# octanis_eps_v03.net
KiCad netlist of a schematic drawn in EAGLE
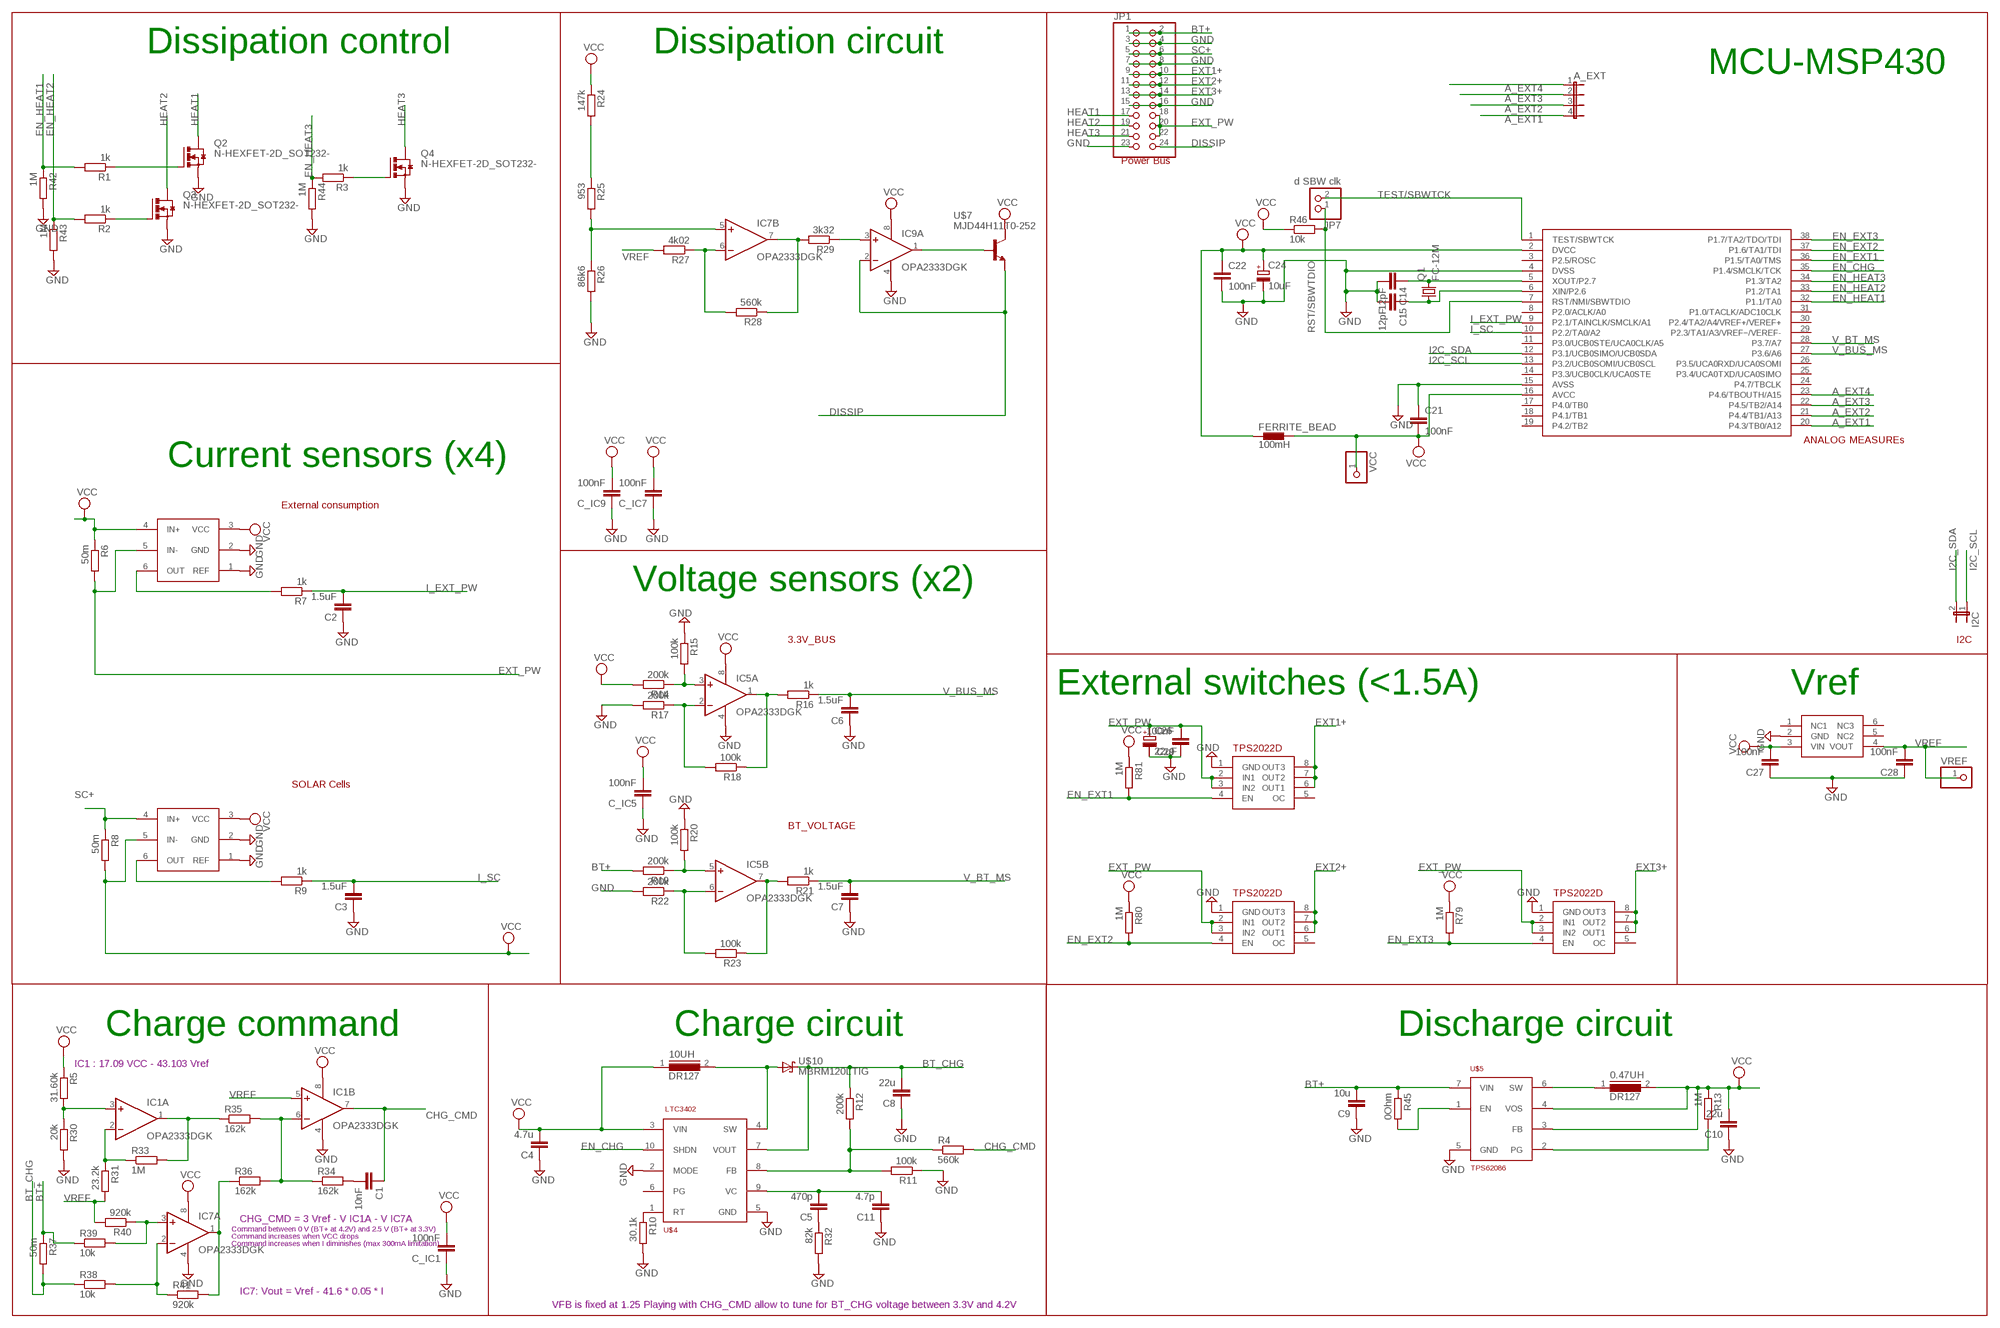
[diagram p0: schematic, sheet 1]

(export (version "E")
  (design (tool "Eeschema 10.0.6"))
  (components
    (comp (ref "0.47UH")
      (value "DR127")
      (footprint "eagle-import:DR127")
      (libsource (lib "eagle-import") (part "DR127"))
    )
    (comp (ref "10UH")
      (value "DR127")
      (footprint "eagle-import:DR127")
      (libsource (lib "eagle-import") (part "DR127"))
    )
    (comp (ref "A_EXT")
      (value "JP4E")
      (footprint "eagle-import:JP4")
      (libsource (lib "eagle-import") (part "JP4E"))
    )
    (comp (ref "C1")
      (value "10nF")
      (footprint "eagle-import:C0603")
      (libsource (lib "eagle-import") (part "C-EUC0603"))
    )
    (comp (ref "C2")
      (value "1.5uF")
      (footprint "eagle-import:C0603")
      (libsource (lib "eagle-import") (part "C-EUC0603"))
    )
    (comp (ref "C3")
      (value "1.5uF")
      (footprint "eagle-import:C0603")
      (libsource (lib "eagle-import") (part "C-EUC0603"))
    )
    (comp (ref "C4")
      (value "4.7u")
      (footprint "eagle-import:C1206")
      (libsource (lib "eagle-import") (part "C-EUC1206"))
    )
    (comp (ref "C5")
      (value "470p")
      (footprint "eagle-import:C0603")
      (libsource (lib "eagle-import") (part "C-EUC0603"))
    )
    (comp (ref "C6")
      (value "1.5uF")
      (footprint "eagle-import:C0603")
      (libsource (lib "eagle-import") (part "C-EUC0603"))
    )
    (comp (ref "C7")
      (value "1.5uF")
      (footprint "eagle-import:C0603")
      (libsource (lib "eagle-import") (part "C-EUC0603"))
    )
    (comp (ref "C8")
      (value "22u")
      (footprint "eagle-import:C0603")
      (libsource (lib "eagle-import") (part "C-EUC0603"))
    )
    (comp (ref "C9")
      (value "10u")
      (footprint "eagle-import:C1206")
      (libsource (lib "eagle-import") (part "C-EUC1206"))
    )
    (comp (ref "C10")
      (value "22u")
      (footprint "eagle-import:C1206")
      (libsource (lib "eagle-import") (part "C-EUC1206"))
    )
    (comp (ref "C11")
      (value "4.7p")
      (footprint "eagle-import:C0603")
      (libsource (lib "eagle-import") (part "C-EUC0603"))
    )
    (comp (ref "C14")
      (value "12pF")
      (footprint "eagle-import:C0603")
      (libsource (lib "eagle-import") (part "C-EUC0603"))
    )
    (comp (ref "C15")
      (value "12pF")
      (footprint "eagle-import:C0603")
      (libsource (lib "eagle-import") (part "C-EUC0603"))
    )
    (comp (ref "C21")
      (value "100nF")
      (footprint "eagle-import:C0603")
      (libsource (lib "eagle-import") (part "C-EUC0603"))
    )
    (comp (ref "C22")
      (value "100nF")
      (footprint "eagle-import:C0603")
      (libsource (lib "eagle-import") (part "C-EUC0603"))
    )
    (comp (ref "C24")
      (value "10uF")
      (footprint "eagle-import:A_3216-18R")
      (libsource (lib "eagle-import") (part "CPOL-EUA/3216-18R"))
    )
    (comp (ref "C26")
      (value "22uF")
      (footprint "eagle-import:A_3216-18R")
      (libsource (lib "eagle-import") (part "CPOL-EUA/3216-18R"))
    )
    (comp (ref "C27")
      (value "100nF")
      (footprint "eagle-import:C0603")
      (libsource (lib "eagle-import") (part "C-EUC0603"))
    )
    (comp (ref "C28")
      (value "100nF")
      (footprint "eagle-import:C0603")
      (libsource (lib "eagle-import") (part "C-EUC0603"))
    )
    (comp (ref "C29")
      (value "100nF")
      (footprint "eagle-import:C0603")
      (libsource (lib "eagle-import") (part "C-EUC0603"))
    )
    (comp (ref "C_IC1")
      (value "100nF")
      (footprint "eagle-import:C0603")
      (libsource (lib "eagle-import") (part "C-EUC0603"))
    )
    (comp (ref "C_IC5")
      (value "100nF")
      (footprint "eagle-import:C0603")
      (libsource (lib "eagle-import") (part "C-EUC0603"))
    )
    (comp (ref "C_IC7")
      (value "100nF")
      (footprint "eagle-import:C0603")
      (libsource (lib "eagle-import") (part "C-EUC0603"))
    )
    (comp (ref "C_IC9")
      (value "100nF")
      (footprint "eagle-import:C0603")
      (libsource (lib "eagle-import") (part "C-EUC0603"))
    )
    (comp (ref "FERRITE_BEAD")
      (value "100mH")
      (footprint "eagle-import:0402")
      (libsource (lib "eagle-import") (part "BLM15HD601SN1"))
    )
    (comp (ref "I2C")
      (value "JP1E")
      (footprint "eagle-import:JP1")
      (libsource (lib "eagle-import") (part "JP1E"))
    )
    (comp (ref "IC1")
      (value "OPA2333DGK")
      (footprint "eagle-import:MSOP08")
      (libsource (lib "eagle-import") (part "OPA2333DGK"))
    )
    (comp (ref "IC5")
      (value "OPA2333DGK")
      (footprint "eagle-import:MSOP08")
      (libsource (lib "eagle-import") (part "OPA2333DGK"))
    )
    (comp (ref "IC7")
      (value "OPA2333DGK")
      (footprint "eagle-import:MSOP08")
      (libsource (lib "eagle-import") (part "OPA2333DGK"))
    )
    (comp (ref "IC9")
      (value "OPA2333DGK")
      (footprint "eagle-import:MSOP08")
      (libsource (lib "eagle-import") (part "OPA2333DGK"))
    )
    (comp (ref "JP1")
      (value "PINHD-2X12")
      (footprint "eagle-import:2X12")
      (libsource (lib "eagle-import") (part "PINHD-2X12"))
    )
    (comp (ref "JP7")
      (value "d SBW clk")
      (footprint "eagle-import:1X02")
      (libsource (lib "eagle-import") (part "PINHD-1X2"))
    )
    (comp (ref "Q1")
      (value "FC-12M")
      (footprint "eagle-import:FC-12M")
      (libsource (lib "eagle-import") (part "FC-12M"))
    )
    (comp (ref "Q2")
      (value "N-HEXFET-2D_SOT232-")
      (footprint "eagle-import:SOT223")
      (libsource (lib "eagle-import") (part "N-HEXFET-2D_?-SOT232"))
    )
    (comp (ref "Q3")
      (value "N-HEXFET-2D_SOT232-")
      (footprint "eagle-import:SOT223")
      (libsource (lib "eagle-import") (part "N-HEXFET-2D_?-SOT232"))
    )
    (comp (ref "Q4")
      (value "N-HEXFET-2D_SOT232-")
      (footprint "eagle-import:SOT223")
      (libsource (lib "eagle-import") (part "N-HEXFET-2D_?-SOT232"))
    )
    (comp (ref "R1")
      (value "1k")
      (footprint "eagle-import:R0603")
      (libsource (lib "eagle-import") (part "R-EU_R0603"))
    )
    (comp (ref "R2")
      (value "1k")
      (footprint "eagle-import:R0603")
      (libsource (lib "eagle-import") (part "R-EU_R0603"))
    )
    (comp (ref "R3")
      (value "1k")
      (footprint "eagle-import:R0603")
      (libsource (lib "eagle-import") (part "R-EU_R0603"))
    )
    (comp (ref "R4")
      (value "560k")
      (footprint "eagle-import:R0603")
      (libsource (lib "eagle-import") (part "R-EU_R0603"))
    )
    (comp (ref "R5")
      (value "31.60k")
      (footprint "eagle-import:R0603")
      (libsource (lib "eagle-import") (part "R-EU_R0603"))
    )
    (comp (ref "R6")
      (value "50m")
      (footprint "eagle-import:R1206")
      (libsource (lib "eagle-import") (part "R-EU_R1206"))
    )
    (comp (ref "R7")
      (value "1k")
      (footprint "eagle-import:R0603")
      (libsource (lib "eagle-import") (part "R-EU_R0603"))
    )
    (comp (ref "R8")
      (value "50m")
      (footprint "eagle-import:R1206")
      (libsource (lib "eagle-import") (part "R-EU_R1206"))
    )
    (comp (ref "R9")
      (value "1k")
      (footprint "eagle-import:R0603")
      (libsource (lib "eagle-import") (part "R-EU_R0603"))
    )
    (comp (ref "R10")
      (value "30.1k")
      (footprint "eagle-import:R0603")
      (libsource (lib "eagle-import") (part "R-EU_R0603"))
    )
    (comp (ref "R11")
      (value "100k")
      (footprint "eagle-import:R0603")
      (libsource (lib "eagle-import") (part "R-EU_R0603"))
    )
    (comp (ref "R12")
      (value "200k")
      (footprint "eagle-import:R0603")
      (libsource (lib "eagle-import") (part "R-EU_R0603"))
    )
    (comp (ref "R13")
      (value "1M")
      (footprint "eagle-import:R0603")
      (libsource (lib "eagle-import") (part "R-EU_R0603"))
    )
    (comp (ref "R14")
      (value "200k")
      (footprint "eagle-import:R0603")
      (libsource (lib "eagle-import") (part "R-EU_R0603"))
    )
    (comp (ref "R15")
      (value "100k")
      (footprint "eagle-import:R0603")
      (libsource (lib "eagle-import") (part "R-EU_R0603"))
    )
    (comp (ref "R16")
      (value "1k")
      (footprint "eagle-import:R0603")
      (libsource (lib "eagle-import") (part "R-EU_R0603"))
    )
    (comp (ref "R17")
      (value "200k")
      (footprint "eagle-import:R0603")
      (libsource (lib "eagle-import") (part "R-EU_R0603"))
    )
    (comp (ref "R18")
      (value "100k")
      (footprint "eagle-import:R0603")
      (libsource (lib "eagle-import") (part "R-EU_R0603"))
    )
    (comp (ref "R19")
      (value "200k")
      (footprint "eagle-import:R0603")
      (libsource (lib "eagle-import") (part "R-EU_R0603"))
    )
    (comp (ref "R20")
      (value "100k")
      (footprint "eagle-import:R0603")
      (libsource (lib "eagle-import") (part "R-EU_R0603"))
    )
    (comp (ref "R21")
      (value "1k")
      (footprint "eagle-import:R0603")
      (libsource (lib "eagle-import") (part "R-EU_R0603"))
    )
    (comp (ref "R22")
      (value "200k")
      (footprint "eagle-import:R0603")
      (libsource (lib "eagle-import") (part "R-EU_R0603"))
    )
    (comp (ref "R23")
      (value "100k")
      (footprint "eagle-import:R0603")
      (libsource (lib "eagle-import") (part "R-EU_R0603"))
    )
    (comp (ref "R24")
      (value "147k")
      (footprint "eagle-import:R0603")
      (libsource (lib "eagle-import") (part "R-EU_R0603"))
    )
    (comp (ref "R25")
      (value "953")
      (footprint "eagle-import:R0603")
      (libsource (lib "eagle-import") (part "R-EU_R0603"))
    )
    (comp (ref "R26")
      (value "86k6")
      (footprint "eagle-import:R0603")
      (libsource (lib "eagle-import") (part "R-EU_R0603"))
    )
    (comp (ref "R27")
      (value "4k02")
      (footprint "eagle-import:R0603")
      (libsource (lib "eagle-import") (part "R-EU_R0603"))
    )
    (comp (ref "R28")
      (value "560k")
      (footprint "eagle-import:R0603")
      (libsource (lib "eagle-import") (part "R-EU_R0603"))
    )
    (comp (ref "R29")
      (value "3k32")
      (footprint "eagle-import:R0603")
      (libsource (lib "eagle-import") (part "R-EU_R0603"))
    )
    (comp (ref "R30")
      (value "20k")
      (footprint "eagle-import:R0603")
      (libsource (lib "eagle-import") (part "R-EU_R0603"))
    )
    (comp (ref "R31")
      (value "23.2k")
      (footprint "eagle-import:R0603")
      (libsource (lib "eagle-import") (part "R-EU_R0603"))
    )
    (comp (ref "R32")
      (value "82k")
      (footprint "eagle-import:R0603")
      (libsource (lib "eagle-import") (part "R-EU_R0603"))
    )
    (comp (ref "R33")
      (value "1M")
      (footprint "eagle-import:R0603")
      (libsource (lib "eagle-import") (part "R-EU_R0603"))
    )
    (comp (ref "R34")
      (value "162k")
      (footprint "eagle-import:R0603")
      (libsource (lib "eagle-import") (part "R-EU_R0603"))
    )
    (comp (ref "R35")
      (value "162k")
      (footprint "eagle-import:R0603")
      (libsource (lib "eagle-import") (part "R-EU_R0603"))
    )
    (comp (ref "R36")
      (value "162k")
      (footprint "eagle-import:R0603")
      (libsource (lib "eagle-import") (part "R-EU_R0603"))
    )
    (comp (ref "R37")
      (value "50m")
      (footprint "eagle-import:R1206")
      (libsource (lib "eagle-import") (part "R-EU_R1206"))
    )
    (comp (ref "R38")
      (value "10k")
      (footprint "eagle-import:R0603")
      (libsource (lib "eagle-import") (part "R-EU_R0603"))
    )
    (comp (ref "R39")
      (value "10k")
      (footprint "eagle-import:R0603")
      (libsource (lib "eagle-import") (part "R-EU_R0603"))
    )
    (comp (ref "R40")
      (value "920k")
      (footprint "eagle-import:R0603")
      (libsource (lib "eagle-import") (part "R-EU_R0603"))
    )
    (comp (ref "R41")
      (value "920k")
      (footprint "eagle-import:R0603")
      (libsource (lib "eagle-import") (part "R-EU_R0603"))
    )
    (comp (ref "R42")
      (value "1M")
      (footprint "eagle-import:R0603")
      (libsource (lib "eagle-import") (part "R-EU_R0603"))
    )
    (comp (ref "R43")
      (value "1M")
      (footprint "eagle-import:R0603")
      (libsource (lib "eagle-import") (part "R-EU_R0603"))
    )
    (comp (ref "R44")
      (value "1M")
      (footprint "eagle-import:R0603")
      (libsource (lib "eagle-import") (part "R-EU_R0603"))
    )
    (comp (ref "R45")
      (value "0Ohm")
      (footprint "eagle-import:R0603")
      (libsource (lib "eagle-import") (part "R-EU_R0603"))
    )
    (comp (ref "R46")
      (value "10k")
      (footprint "eagle-import:R0603")
      (libsource (lib "eagle-import") (part "R-EU_R0603"))
    )
    (comp (ref "R79")
      (value "1M")
      (footprint "eagle-import:R0603")
      (libsource (lib "eagle-import") (part "R-EU_R0603"))
    )
    (comp (ref "R80")
      (value "1M")
      (footprint "eagle-import:R0603")
      (libsource (lib "eagle-import") (part "R-EU_R0603"))
    )
    (comp (ref "R81")
      (value "1M")
      (footprint "eagle-import:R0603")
      (libsource (lib "eagle-import") (part "R-EU_R0603"))
    )
    (comp (ref "U$2")
      (value "INA213")
      (footprint "eagle-import:SC70-6")
      (libsource (lib "eagle-import") (part "INA213"))
    )
    (comp (ref "U$3")
      (value "INA213")
      (footprint "eagle-import:SC70-6")
      (libsource (lib "eagle-import") (part "INA213"))
    )
    (comp (ref "U$4")
      (value "LTC3402")
      (footprint "eagle-import:MSOP10")
      (libsource (lib "eagle-import") (part "LTC3402"))
    )
    (comp (ref "U$5")
      (value "TPS62086")
      (footprint "eagle-import:QFN-7")
      (libsource (lib "eagle-import") (part "TPS62086"))
    )
    (comp (ref "U$6")
      (value "MSP430G2544")
      (footprint "eagle-import:TSSOP38_MSPGXX44_SERIES")
      (libsource (lib "eagle-import") (part "MSP430G2544"))
    )
    (comp (ref "U$7")
      (value "MJD44H11T0-252")
      (footprint "eagle-import:TO252")
      (libsource (lib "eagle-import") (part "MJD44H11T0-252"))
    )
    (comp (ref "U$10")
      (value "MBRM120LTIG")
      (footprint "eagle-import:DO216AA")
      (libsource (lib "eagle-import") (part "MBRM120LTIG"))
    )
    (comp (ref "U$16")
      (value "TPS2022D")
      (footprint "eagle-import:SO8")
      (libsource (lib "eagle-import") (part "TPS2022D"))
    )
    (comp (ref "U$17")
      (value "TPS2022D")
      (footprint "eagle-import:SO8")
      (libsource (lib "eagle-import") (part "TPS2022D"))
    )
    (comp (ref "U$18")
      (value "TPS2022D")
      (footprint "eagle-import:SO8")
      (libsource (lib "eagle-import") (part "TPS2022D"))
    )
    (comp (ref "U$19")
      (value "ADR127B")
      (footprint "eagle-import:TSOT23-6")
      (libsource (lib "eagle-import") (part "ADR127B"))
    )
    (comp (ref "VCC")
      (value "PINHD-1X1")
      (footprint "eagle-import:1X01")
      (libsource (lib "eagle-import") (part "PINHD-1X1"))
    )
    (comp (ref "VREF")
      (value "PINHD-1X1")
      (footprint "eagle-import:1X01")
      (libsource (lib "eagle-import") (part "PINHD-1X1"))
    )
  )
  (nets
    (net (code "1") (name "/A_EXT1") (class "Default")
      (node (ref "A_EXT") (pin "4") (pinfunction "4_4") (pintype "passive"))
      (node (ref "U$6") (pin "20") (pinfunction "P4.3/TB0/A12_20") (pintype "bidirectional"))
    )
    (net (code "2") (name "/A_EXT2") (class "Default")
      (node (ref "A_EXT") (pin "3") (pinfunction "3_3") (pintype "passive"))
      (node (ref "U$6") (pin "21") (pinfunction "P4.4/TB1/A13_21") (pintype "bidirectional"))
    )
    (net (code "3") (name "/A_EXT3") (class "Default")
      (node (ref "A_EXT") (pin "2") (pinfunction "2_2") (pintype "passive"))
      (node (ref "U$6") (pin "22") (pinfunction "P4.5/TB2/A14_22") (pintype "bidirectional"))
    )
    (net (code "4") (name "/A_EXT4") (class "Default")
      (node (ref "A_EXT") (pin "1") (pinfunction "1_1") (pintype "passive"))
      (node (ref "U$6") (pin "23") (pinfunction "P4.6/TBOUTH/A15_23") (pintype "bidirectional"))
    )
    (net (code "5") (name "/BT+") (class "Default")
      (node (ref "C9") (pin "2") (pinfunction "2_2") (pintype "passive"))
      (node (ref "JP1") (pin "1") (pinfunction "1_1") (pintype "passive"))
      (node (ref "JP1") (pin "2") (pinfunction "2_2") (pintype "passive"))
      (node (ref "R19") (pin "2") (pinfunction "2_2") (pintype "passive"))
      (node (ref "R37") (pin "1") (pinfunction "1_1") (pintype "passive"))
      (node (ref "R39") (pin "1") (pinfunction "1_1") (pintype "passive"))
      (node (ref "R45") (pin "1") (pinfunction "1_1") (pintype "passive"))
      (node (ref "U$5") (pin "7") (pinfunction "VIN_7") (pintype "bidirectional"))
    )
    (net (code "6") (name "/BT_CHG") (class "Default")
      (node (ref "C8") (pin "2") (pinfunction "2_2") (pintype "passive"))
      (node (ref "R12") (pin "1") (pinfunction "1_1") (pintype "passive"))
      (node (ref "R37") (pin "2") (pinfunction "2_2") (pintype "passive"))
      (node (ref "R38") (pin "1") (pinfunction "1_1") (pintype "passive"))
      (node (ref "U$10") (pin "C") (pinfunction "K_C") (pintype "passive"))
      (node (ref "U$4") (pin "7") (pinfunction "VOUT_7") (pintype "bidirectional"))
    )
    (net (code "7") (name "/CHG_CMD") (class "Default")
      (node (ref "C1") (pin "1") (pinfunction "1_1") (pintype "passive"))
      (node (ref "IC1") (pin "7") (pinfunction "OUT_7") (pintype "output"))
      (node (ref "R4") (pin "2") (pinfunction "2_2") (pintype "passive"))
    )
    (net (code "8") (name "/DISSIP") (class "Default")
      (node (ref "IC9") (pin "2") (pinfunction "-IN_2") (pintype "input"))
      (node (ref "JP1") (pin "24") (pinfunction "24_24") (pintype "passive"))
      (node (ref "U$7") (pin "3") (pinfunction "E_3") (pintype "passive"))
    )
    (net (code "9") (name "/EN_CHG") (class "Default")
      (node (ref "U$4") (pin "10") (pinfunction "SHDN_10") (pintype "bidirectional"))
      (node (ref "U$6") (pin "35") (pinfunction "P1.4/SMCLK/TCK_35") (pintype "bidirectional"))
    )
    (net (code "10") (name "/EN_EXT1") (class "Default")
      (node (ref "R81") (pin "2") (pinfunction "2_2") (pintype "passive"))
      (node (ref "U$16") (pin "4") (pinfunction "EN_4") (pintype "bidirectional"))
      (node (ref "U$6") (pin "36") (pinfunction "P1.5/TA0/TMS_36") (pintype "bidirectional"))
    )
    (net (code "11") (name "/EN_EXT2") (class "Default")
      (node (ref "R80") (pin "2") (pinfunction "2_2") (pintype "passive"))
      (node (ref "U$17") (pin "4") (pinfunction "EN_4") (pintype "bidirectional"))
      (node (ref "U$6") (pin "37") (pinfunction "P1.6/TA1/TDI_37") (pintype "bidirectional"))
    )
    (net (code "12") (name "/EN_EXT3") (class "Default")
      (node (ref "R79") (pin "2") (pinfunction "2_2") (pintype "passive"))
      (node (ref "U$18") (pin "4") (pinfunction "EN_4") (pintype "bidirectional"))
      (node (ref "U$6") (pin "38") (pinfunction "P1.7/TA2/TDO/TDI_38") (pintype "bidirectional"))
    )
    (net (code "13") (name "/EN_HEAT1") (class "Default")
      (node (ref "R1") (pin "2") (pinfunction "2_2") (pintype "passive"))
      (node (ref "R42") (pin "1") (pinfunction "1_1") (pintype "passive"))
      (node (ref "U$6") (pin "32") (pinfunction "P1.1/TA0_32") (pintype "bidirectional"))
    )
    (net (code "14") (name "/EN_HEAT2") (class "Default")
      (node (ref "R2") (pin "2") (pinfunction "2_2") (pintype "passive"))
      (node (ref "R43") (pin "1") (pinfunction "1_1") (pintype "passive"))
      (node (ref "U$6") (pin "33") (pinfunction "P1.2/TA1_33") (pintype "bidirectional"))
    )
    (net (code "15") (name "/EN_HEAT3") (class "Default")
      (node (ref "R3") (pin "2") (pinfunction "2_2") (pintype "passive"))
      (node (ref "R44") (pin "1") (pinfunction "1_1") (pintype "passive"))
      (node (ref "U$6") (pin "34") (pinfunction "P1.3/TA2_34") (pintype "bidirectional"))
    )
    (net (code "16") (name "/EXT1+") (class "Default")
      (node (ref "JP1") (pin "10") (pinfunction "10_10") (pintype "passive"))
      (node (ref "JP1") (pin "9") (pinfunction "9_9") (pintype "passive"))
      (node (ref "U$16") (pin "6") (pinfunction "OUT1_6") (pintype "bidirectional"))
      (node (ref "U$16") (pin "7") (pinfunction "OUT2_7") (pintype "bidirectional"))
      (node (ref "U$16") (pin "8") (pinfunction "OUT3_8") (pintype "bidirectional"))
    )
    (net (code "17") (name "/EXT2+") (class "Default")
      (node (ref "JP1") (pin "11") (pinfunction "11_11") (pintype "passive"))
      (node (ref "JP1") (pin "12") (pinfunction "12_12") (pintype "passive"))
      (node (ref "U$17") (pin "6") (pinfunction "OUT1_6") (pintype "bidirectional"))
      (node (ref "U$17") (pin "7") (pinfunction "OUT2_7") (pintype "bidirectional"))
      (node (ref "U$17") (pin "8") (pinfunction "OUT3_8") (pintype "bidirectional"))
    )
    (net (code "18") (name "/EXT3+") (class "Default")
      (node (ref "JP1") (pin "13") (pinfunction "13_13") (pintype "passive"))
      (node (ref "JP1") (pin "14") (pinfunction "14_14") (pintype "passive"))
      (node (ref "U$18") (pin "6") (pinfunction "OUT1_6") (pintype "bidirectional"))
      (node (ref "U$18") (pin "7") (pinfunction "OUT2_7") (pintype "bidirectional"))
      (node (ref "U$18") (pin "8") (pinfunction "OUT3_8") (pintype "bidirectional"))
    )
    (net (code "19") (name "/EXT_PW") (class "Default")
      (node (ref "C26") (pin "+") (pinfunction "+_+") (pintype "passive"))
      (node (ref "C29") (pin "2") (pinfunction "2_2") (pintype "passive"))
      (node (ref "JP1") (pin "18") (pinfunction "18_18") (pintype "passive"))
      (node (ref "JP1") (pin "20") (pinfunction "20_20") (pintype "passive"))
      (node (ref "JP1") (pin "22") (pinfunction "22_22") (pintype "passive"))
      (node (ref "R6") (pin "2") (pinfunction "2_2") (pintype "passive"))
      (node (ref "U$16") (pin "2") (pinfunction "IN1_2") (pintype "bidirectional"))
      (node (ref "U$16") (pin "3") (pinfunction "IN2_3") (pintype "bidirectional"))
      (node (ref "U$17") (pin "2") (pinfunction "IN1_2") (pintype "bidirectional"))
      (node (ref "U$17") (pin "3") (pinfunction "IN2_3") (pintype "bidirectional"))
      (node (ref "U$18") (pin "2") (pinfunction "IN1_2") (pintype "bidirectional"))
      (node (ref "U$18") (pin "3") (pinfunction "IN2_3") (pintype "bidirectional"))
      (node (ref "U$2") (pin "5") (pinfunction "IN-_5") (pintype "bidirectional"))
    )
    (net (code "20") (name "/HEAT1") (class "Default")
      (node (ref "JP1") (pin "17") (pinfunction "17_17") (pintype "passive"))
      (node (ref "Q2") (pin "2") (pinfunction "D_2") (pintype "passive"))
      (node (ref "Q2") (pin "4") (pinfunction "D_4") (pintype "passive"))
    )
    (net (code "21") (name "/HEAT2") (class "Default")
      (node (ref "JP1") (pin "19") (pinfunction "19_19") (pintype "passive"))
      (node (ref "Q3") (pin "2") (pinfunction "D_2") (pintype "passive"))
      (node (ref "Q3") (pin "4") (pinfunction "D_4") (pintype "passive"))
    )
    (net (code "22") (name "/HEAT3") (class "Default")
      (node (ref "JP1") (pin "21") (pinfunction "21_21") (pintype "passive"))
      (node (ref "Q4") (pin "2") (pinfunction "D_2") (pintype "passive"))
      (node (ref "Q4") (pin "4") (pinfunction "D_4") (pintype "passive"))
    )
    (net (code "23") (name "/I2C_SCL") (class "Default")
      (node (ref "I2C") (pin "1") (pinfunction "1_1") (pintype "passive"))
      (node (ref "U$6") (pin "13") (pinfunction "P3.2/UCB0SOMI/UCB0SCL_13") (pintype "bidirectional"))
    )
    (net (code "24") (name "/I2C_SDA") (class "Default")
      (node (ref "I2C") (pin "2") (pinfunction "2_2") (pintype "passive"))
      (node (ref "U$6") (pin "12") (pinfunction "P3.1/UCB0SIMO/UCB0SDA_12") (pintype "bidirectional"))
    )
    (net (code "25") (name "/I_EXT_PW") (class "Default")
      (node (ref "C2") (pin "2") (pinfunction "2_2") (pintype "passive"))
      (node (ref "R7") (pin "1") (pinfunction "1_1") (pintype "passive"))
      (node (ref "U$6") (pin "9") (pinfunction "P2.1/TAINCLK/SMCLK/A1_9") (pintype "bidirectional"))
    )
    (net (code "26") (name "/I_SC") (class "Default")
      (node (ref "C3") (pin "2") (pinfunction "2_2") (pintype "passive"))
      (node (ref "R9") (pin "1") (pinfunction "1_1") (pintype "passive"))
      (node (ref "U$6") (pin "10") (pinfunction "P2.2/TA0/A2_10") (pintype "bidirectional"))
    )
    (net (code "27") (name "/RST{slash}SBWTDIO") (class "Default")
      (node (ref "JP7") (pin "1") (pinfunction "1_1") (pintype "passive"))
      (node (ref "R46") (pin "2") (pinfunction "2_2") (pintype "passive"))
      (node (ref "U$6") (pin "7") (pinfunction "RST/NMI/SBWTDIO_7") (pintype "bidirectional"))
    )
    (net (code "28") (name "/SC+") (class "Default")
      (node (ref "JP1") (pin "5") (pinfunction "5_5") (pintype "passive"))
      (node (ref "JP1") (pin "6") (pinfunction "6_6") (pintype "passive"))
      (node (ref "R8") (pin "1") (pinfunction "1_1") (pintype "passive"))
      (node (ref "U$3") (pin "4") (pinfunction "IN+_4") (pintype "bidirectional"))
    )
    (net (code "29") (name "/TEST{slash}SBWTCK") (class "Default")
      (node (ref "JP7") (pin "2") (pinfunction "2_2") (pintype "passive"))
      (node (ref "U$6") (pin "1") (pinfunction "TEST/SBWTCK_1") (pintype "bidirectional"))
    )
    (net (code "30") (name "/VREF") (class "Default")
      (node (ref "C28") (pin "2") (pinfunction "2_2") (pintype "passive"))
      (node (ref "IC1") (pin "5") (pinfunction "+IN_5") (pintype "input"))
      (node (ref "R27") (pin "2") (pinfunction "2_2") (pintype "passive"))
      (node (ref "R31") (pin "2") (pinfunction "2_2") (pintype "passive"))
      (node (ref "R40") (pin "2") (pinfunction "2_2") (pintype "passive"))
      (node (ref "U$19") (pin "4") (pinfunction "VOUT_4") (pintype "bidirectional"))
      (node (ref "VREF") (pin "1") (pinfunction "1_1") (pintype "passive"))
    )
    (net (code "31") (name "/V_BT_MS") (class "Default")
      (node (ref "C7") (pin "2") (pinfunction "2_2") (pintype "passive"))
      (node (ref "R21") (pin "1") (pinfunction "1_1") (pintype "passive"))
      (node (ref "U$6") (pin "28") (pinfunction "P3.7/A7_28") (pintype "bidirectional"))
    )
    (net (code "32") (name "/V_BUS_MS") (class "Default")
      (node (ref "C6") (pin "2") (pinfunction "2_2") (pintype "passive"))
      (node (ref "R16") (pin "1") (pinfunction "1_1") (pintype "passive"))
      (node (ref "U$6") (pin "27") (pinfunction "P3.6/A6_27") (pintype "bidirectional"))
    )
    (net (code "33") (name "GND") (class "Default")
      (node (ref "C10") (pin "1") (pinfunction "1_1") (pintype "passive"))
      (node (ref "C11") (pin "1") (pinfunction "1_1") (pintype "passive"))
      (node (ref "C14") (pin "2") (pinfunction "2_2") (pintype "passive"))
      (node (ref "C15") (pin "2") (pinfunction "2_2") (pintype "passive"))
      (node (ref "C2") (pin "1") (pinfunction "1_1") (pintype "passive"))
      (node (ref "C21") (pin "1") (pinfunction "1_1") (pintype "passive"))
      (node (ref "C22") (pin "2") (pinfunction "2_2") (pintype "passive"))
      (node (ref "C24") (pin "-") (pinfunction "-_-") (pintype "passive"))
      (node (ref "C26") (pin "-") (pinfunction "-_-") (pintype "passive"))
      (node (ref "C27") (pin "1") (pinfunction "1_1") (pintype "passive"))
      (node (ref "C28") (pin "1") (pinfunction "1_1") (pintype "passive"))
      (node (ref "C29") (pin "1") (pinfunction "1_1") (pintype "passive"))
      (node (ref "C3") (pin "1") (pinfunction "1_1") (pintype "passive"))
      (node (ref "C4") (pin "1") (pinfunction "1_1") (pintype "passive"))
      (node (ref "C6") (pin "1") (pinfunction "1_1") (pintype "passive"))
      (node (ref "C7") (pin "1") (pinfunction "1_1") (pintype "passive"))
      (node (ref "C8") (pin "1") (pinfunction "1_1") (pintype "passive"))
      (node (ref "C9") (pin "1") (pinfunction "1_1") (pintype "passive"))
      (node (ref "C_IC1") (pin "1") (pinfunction "1_1") (pintype "passive"))
      (node (ref "C_IC5") (pin "1") (pinfunction "1_1") (pintype "passive"))
      (node (ref "C_IC7") (pin "1") (pinfunction "1_1") (pintype "passive"))
      (node (ref "C_IC9") (pin "1") (pinfunction "1_1") (pintype "passive"))
      (node (ref "IC1") (pin "4") (pinfunction "V-_4") (pintype "power_in"))
      (node (ref "IC5") (pin "4") (pinfunction "V-_4") (pintype "power_in"))
      (node (ref "IC7") (pin "4") (pinfunction "V-_4") (pintype "power_in"))
      (node (ref "IC9") (pin "4") (pinfunction "V-_4") (pintype "power_in"))
      (node (ref "JP1") (pin "15") (pinfunction "15_15") (pintype "passive"))
      (node (ref "JP1") (pin "16") (pinfunction "16_16") (pintype "passive"))
      (node (ref "JP1") (pin "23") (pinfunction "23_23") (pintype "passive"))
      (node (ref "JP1") (pin "3") (pinfunction "3_3") (pintype "passive"))
      (node (ref "JP1") (pin "4") (pinfunction "4_4") (pintype "passive"))
      (node (ref "JP1") (pin "7") (pinfunction "7_7") (pintype "passive"))
      (node (ref "JP1") (pin "8") (pinfunction "8_8") (pintype "passive"))
      (node (ref "Q2") (pin "3") (pinfunction "S_3") (pintype "passive"))
      (node (ref "Q3") (pin "3") (pinfunction "S_3") (pintype "passive"))
      (node (ref "Q4") (pin "3") (pinfunction "S_3") (pintype "passive"))
      (node (ref "R10") (pin "2") (pinfunction "2_2") (pintype "passive"))
      (node (ref "R11") (pin "1") (pinfunction "1_1") (pintype "passive"))
      (node (ref "R15") (pin "1") (pinfunction "1_1") (pintype "passive"))
      (node (ref "R17") (pin "2") (pinfunction "2_2") (pintype "passive"))
      (node (ref "R20") (pin "1") (pinfunction "1_1") (pintype "passive"))
      (node (ref "R22") (pin "2") (pinfunction "2_2") (pintype "passive"))
      (node (ref "R26") (pin "2") (pinfunction "2_2") (pintype "passive"))
      (node (ref "R30") (pin "2") (pinfunction "2_2") (pintype "passive"))
      (node (ref "R32") (pin "2") (pinfunction "2_2") (pintype "passive"))
      (node (ref "R42") (pin "2") (pinfunction "2_2") (pintype "passive"))
      (node (ref "R43") (pin "2") (pinfunction "2_2") (pintype "passive"))
      (node (ref "R44") (pin "2") (pinfunction "2_2") (pintype "passive"))
      (node (ref "U$16") (pin "1") (pinfunction "GND_1") (pintype "bidirectional"))
      (node (ref "U$17") (pin "1") (pinfunction "GND_1") (pintype "bidirectional"))
      (node (ref "U$18") (pin "1") (pinfunction "GND_1") (pintype "bidirectional"))
      (node (ref "U$19") (pin "2") (pinfunction "GND_2") (pintype "bidirectional"))
      (node (ref "U$2") (pin "1") (pinfunction "REF_1") (pintype "bidirectional"))
      (node (ref "U$2") (pin "2") (pinfunction "GND_2") (pintype "bidirectional"))
      (node (ref "U$3") (pin "1") (pinfunction "REF_1") (pintype "bidirectional"))
      (node (ref "U$3") (pin "2") (pinfunction "GND_2") (pintype "bidirectional"))
      (node (ref "U$4") (pin "2") (pinfunction "MODE_2") (pintype "bidirectional"))
      (node (ref "U$4") (pin "5") (pinfunction "GND_5") (pintype "bidirectional"))
      (node (ref "U$5") (pin "5") (pinfunction "GND_5") (pintype "bidirectional"))
      (node (ref "U$6") (pin "15") (pinfunction "AVSS_15") (pintype "bidirectional"))
      (node (ref "U$6") (pin "4") (pinfunction "DVSS_4") (pintype "bidirectional"))
    )
    (net (code "34") (name "Net-(C1-Pad2)") (class "Default")
      (node (ref "C1") (pin "2") (pinfunction "2_2") (pintype "passive"))
      (node (ref "R34") (pin "2") (pinfunction "2_2") (pintype "passive"))
    )
    (net (code "35") (name "Net-(C5-Pad1)") (class "Default")
      (node (ref "C5") (pin "1") (pinfunction "1_1") (pintype "passive"))
      (node (ref "R32") (pin "1") (pinfunction "1_1") (pintype "passive"))
    )
    (net (code "36") (name "Net-(IC1A-+IN)") (class "Default")
      (node (ref "IC1") (pin "3") (pinfunction "+IN_3") (pintype "input"))
      (node (ref "R30") (pin "1") (pinfunction "1_1") (pintype "passive"))
      (node (ref "R5") (pin "2") (pinfunction "2_2") (pintype "passive"))
    )
    (net (code "37") (name "Net-(IC1A--IN)") (class "Default")
      (node (ref "IC1") (pin "2") (pinfunction "-IN_2") (pintype "input"))
      (node (ref "R31") (pin "1") (pinfunction "1_1") (pintype "passive"))
      (node (ref "R33") (pin "1") (pinfunction "1_1") (pintype "passive"))
    )
    (net (code "38") (name "Net-(IC1A-OUT)") (class "Default")
      (node (ref "IC1") (pin "1") (pinfunction "OUT_1") (pintype "output"))
      (node (ref "R33") (pin "2") (pinfunction "2_2") (pintype "passive"))
      (node (ref "R35") (pin "1") (pinfunction "1_1") (pintype "passive"))
    )
    (net (code "39") (name "Net-(IC1B--IN)") (class "Default")
      (node (ref "IC1") (pin "6") (pinfunction "-IN_6") (pintype "input"))
      (node (ref "R34") (pin "1") (pinfunction "1_1") (pintype "passive"))
      (node (ref "R35") (pin "2") (pinfunction "2_2") (pintype "passive"))
      (node (ref "R36") (pin "2") (pinfunction "2_2") (pintype "passive"))
    )
    (net (code "40") (name "Net-(IC5A-+IN)") (class "Default")
      (node (ref "IC5") (pin "3") (pinfunction "+IN_3") (pintype "input"))
      (node (ref "R14") (pin "1") (pinfunction "1_1") (pintype "passive"))
      (node (ref "R15") (pin "2") (pinfunction "2_2") (pintype "passive"))
    )
    (net (code "41") (name "Net-(IC5A--IN)") (class "Default")
      (node (ref "IC5") (pin "2") (pinfunction "-IN_2") (pintype "input"))
      (node (ref "R17") (pin "1") (pinfunction "1_1") (pintype "passive"))
      (node (ref "R18") (pin "2") (pinfunction "2_2") (pintype "passive"))
    )
    (net (code "42") (name "Net-(IC5A-OUT)") (class "Default")
      (node (ref "IC5") (pin "1") (pinfunction "OUT_1") (pintype "output"))
      (node (ref "R16") (pin "2") (pinfunction "2_2") (pintype "passive"))
      (node (ref "R18") (pin "1") (pinfunction "1_1") (pintype "passive"))
    )
    (net (code "43") (name "Net-(IC5B-+IN)") (class "Default")
      (node (ref "IC5") (pin "5") (pinfunction "+IN_5") (pintype "input"))
      (node (ref "R19") (pin "1") (pinfunction "1_1") (pintype "passive"))
      (node (ref "R20") (pin "2") (pinfunction "2_2") (pintype "passive"))
    )
    (net (code "44") (name "Net-(IC5B--IN)") (class "Default")
      (node (ref "IC5") (pin "6") (pinfunction "-IN_6") (pintype "input"))
      (node (ref "R22") (pin "1") (pinfunction "1_1") (pintype "passive"))
      (node (ref "R23") (pin "2") (pinfunction "2_2") (pintype "passive"))
    )
    (net (code "45") (name "Net-(IC5B-OUT)") (class "Default")
      (node (ref "IC5") (pin "7") (pinfunction "OUT_7") (pintype "output"))
      (node (ref "R21") (pin "2") (pinfunction "2_2") (pintype "passive"))
      (node (ref "R23") (pin "1") (pinfunction "1_1") (pintype "passive"))
    )
    (net (code "46") (name "Net-(IC7A-+IN)") (class "Default")
      (node (ref "IC7") (pin "3") (pinfunction "+IN_3") (pintype "input"))
      (node (ref "R39") (pin "2") (pinfunction "2_2") (pintype "passive"))
      (node (ref "R40") (pin "1") (pinfunction "1_1") (pintype "passive"))
    )
    (net (code "47") (name "Net-(IC7A--IN)") (class "Default")
      (node (ref "IC7") (pin "2") (pinfunction "-IN_2") (pintype "input"))
      (node (ref "R38") (pin "2") (pinfunction "2_2") (pintype "passive"))
      (node (ref "R41") (pin "1") (pinfunction "1_1") (pintype "passive"))
    )
    (net (code "48") (name "Net-(IC7A-OUT)") (class "Default")
      (node (ref "IC7") (pin "1") (pinfunction "OUT_1") (pintype "output"))
      (node (ref "R36") (pin "1") (pinfunction "1_1") (pintype "passive"))
      (node (ref "R41") (pin "2") (pinfunction "2_2") (pintype "passive"))
    )
    (net (code "49") (name "Net-(IC7B-+IN)") (class "Default")
      (node (ref "IC7") (pin "5") (pinfunction "+IN_5") (pintype "input"))
      (node (ref "R25") (pin "2") (pinfunction "2_2") (pintype "passive"))
      (node (ref "R26") (pin "1") (pinfunction "1_1") (pintype "passive"))
    )
    (net (code "50") (name "Net-(IC7B--IN)") (class "Default")
      (node (ref "IC7") (pin "6") (pinfunction "-IN_6") (pintype "input"))
      (node (ref "R27") (pin "1") (pinfunction "1_1") (pintype "passive"))
      (node (ref "R28") (pin "2") (pinfunction "2_2") (pintype "passive"))
    )
    (net (code "51") (name "Net-(IC7B-OUT)") (class "Default")
      (node (ref "IC7") (pin "7") (pinfunction "OUT_7") (pintype "output"))
      (node (ref "R28") (pin "1") (pinfunction "1_1") (pintype "passive"))
      (node (ref "R29") (pin "2") (pinfunction "2_2") (pintype "passive"))
    )
    (net (code "52") (name "Net-(IC9A-+IN)") (class "Default")
      (node (ref "IC9") (pin "3") (pinfunction "+IN_3") (pintype "input"))
      (node (ref "R29") (pin "1") (pinfunction "1_1") (pintype "passive"))
    )
    (net (code "53") (name "Net-(IC9A-OUT)") (class "Default")
      (node (ref "IC9") (pin "1") (pinfunction "OUT_1") (pintype "output"))
      (node (ref "U$7") (pin "1") (pinfunction "B_1") (pintype "passive"))
    )
    (net (code "54") (name "Net-(Q2-G)") (class "Default")
      (node (ref "Q2") (pin "1") (pinfunction "G_1") (pintype "passive"))
      (node (ref "R1") (pin "1") (pinfunction "1_1") (pintype "passive"))
    )
    (net (code "55") (name "Net-(Q3-G)") (class "Default")
      (node (ref "Q3") (pin "1") (pinfunction "G_1") (pintype "passive"))
      (node (ref "R2") (pin "1") (pinfunction "1_1") (pintype "passive"))
    )
    (net (code "56") (name "Net-(Q4-G)") (class "Default")
      (node (ref "Q4") (pin "1") (pinfunction "G_1") (pintype "passive"))
      (node (ref "R3") (pin "1") (pinfunction "1_1") (pintype "passive"))
    )
    (net (code "57") (name "Net-(R24-Pad2)") (class "Default")
      (node (ref "R24") (pin "2") (pinfunction "2_2") (pintype "passive"))
      (node (ref "R25") (pin "1") (pinfunction "1_1") (pintype "passive"))
    )
    (net (code "58") (name "Net-(U$2-OUT)") (class "Default")
      (node (ref "R7") (pin "2") (pinfunction "2_2") (pintype "passive"))
      (node (ref "U$2") (pin "6") (pinfunction "OUT_6") (pintype "bidirectional"))
    )
    (net (code "59") (name "Net-(U$3-OUT)") (class "Default")
      (node (ref "R9") (pin "2") (pinfunction "2_2") (pintype "passive"))
      (node (ref "U$3") (pin "6") (pinfunction "OUT_6") (pintype "bidirectional"))
    )
    (net (code "60") (name "Net-(U$4-FB)") (class "Default")
      (node (ref "R11") (pin "2") (pinfunction "2_2") (pintype "passive"))
      (node (ref "R12") (pin "2") (pinfunction "2_2") (pintype "passive"))
      (node (ref "R4") (pin "1") (pinfunction "1_1") (pintype "passive"))
      (node (ref "U$4") (pin "8") (pinfunction "FB_8") (pintype "bidirectional"))
    )
    (net (code "61") (name "Net-(U$4-RT)") (class "Default")
      (node (ref "R10") (pin "1") (pinfunction "1_1") (pintype "passive"))
      (node (ref "U$4") (pin "1") (pinfunction "RT_1") (pintype "bidirectional"))
    )
    (net (code "62") (name "Net-(U$4-SW)") (class "Default")
      (node (ref "10UH") (pin "2") (pinfunction "2_2") (pintype "passive"))
      (node (ref "U$10") (pin "A") (pinfunction "A_A") (pintype "passive"))
      (node (ref "U$4") (pin "4") (pinfunction "SW_4") (pintype "bidirectional"))
    )
    (net (code "63") (name "Net-(U$4-VC)") (class "Default")
      (node (ref "C11") (pin "2") (pinfunction "2_2") (pintype "passive"))
      (node (ref "C5") (pin "2") (pinfunction "2_2") (pintype "passive"))
      (node (ref "U$4") (pin "9") (pinfunction "VC_9") (pintype "bidirectional"))
    )
    (net (code "64") (name "Net-(U$5-EN)") (class "Default")
      (node (ref "R45") (pin "2") (pinfunction "2_2") (pintype "passive"))
      (node (ref "U$5") (pin "1") (pinfunction "EN_1") (pintype "bidirectional"))
    )
    (net (code "65") (name "Net-(U$5-PG)") (class "Default")
      (node (ref "R13") (pin "2") (pinfunction "2_2") (pintype "passive"))
      (node (ref "U$5") (pin "2") (pinfunction "PG_2") (pintype "bidirectional"))
    )
    (net (code "66") (name "Net-(U$5-SW)") (class "Default")
      (node (ref "0.47UH") (pin "1") (pinfunction "1_1") (pintype "passive"))
      (node (ref "U$5") (pin "6") (pinfunction "SW_6") (pintype "bidirectional"))
    )
    (net (code "67") (name "Net-(U$6-XIN{slash}P2.6)") (class "Default")
      (node (ref "C15") (pin "1") (pinfunction "1_1") (pintype "passive"))
      (node (ref "Q1") (pin "1") (pinfunction "1_1") (pintype "passive"))
      (node (ref "U$6") (pin "6") (pinfunction "XIN/P2.6_6") (pintype "bidirectional"))
    )
    (net (code "68") (name "Net-(U$6-XOUT{slash}P2.7)") (class "Default")
      (node (ref "C14") (pin "1") (pinfunction "1_1") (pintype "passive"))
      (node (ref "Q1") (pin "2") (pinfunction "2_2") (pintype "passive"))
      (node (ref "U$6") (pin "5") (pinfunction "XOUT/P2.7_5") (pintype "bidirectional"))
    )
    (net (code "69") (name "VCC") (class "Default")
      (node (ref "0.47UH") (pin "2") (pinfunction "2_2") (pintype "passive"))
      (node (ref "10UH") (pin "1") (pinfunction "1_1") (pintype "passive"))
      (node (ref "C10") (pin "2") (pinfunction "2_2") (pintype "passive"))
      (node (ref "C21") (pin "2") (pinfunction "2_2") (pintype "passive"))
      (node (ref "C22") (pin "1") (pinfunction "1_1") (pintype "passive"))
      (node (ref "C24") (pin "+") (pinfunction "+_+") (pintype "passive"))
      (node (ref "C27") (pin "2") (pinfunction "2_2") (pintype "passive"))
      (node (ref "C4") (pin "2") (pinfunction "2_2") (pintype "passive"))
      (node (ref "C_IC1") (pin "2") (pinfunction "2_2") (pintype "passive"))
      (node (ref "C_IC5") (pin "2") (pinfunction "2_2") (pintype "passive"))
      (node (ref "C_IC7") (pin "2") (pinfunction "2_2") (pintype "passive"))
      (node (ref "C_IC9") (pin "2") (pinfunction "2_2") (pintype "passive"))
      (node (ref "FERRITE_BEAD") (pin "1") (pinfunction "1_1") (pintype "passive"))
      (node (ref "FERRITE_BEAD") (pin "2") (pinfunction "2_2") (pintype "passive"))
      (node (ref "IC1") (pin "8") (pinfunction "V+_8") (pintype "power_in"))
      (node (ref "IC5") (pin "8") (pinfunction "V+_8") (pintype "power_in"))
      (node (ref "IC7") (pin "8") (pinfunction "V+_8") (pintype "power_in"))
      (node (ref "IC9") (pin "8") (pinfunction "V+_8") (pintype "power_in"))
      (node (ref "R13") (pin "1") (pinfunction "1_1") (pintype "passive"))
      (node (ref "R14") (pin "2") (pinfunction "2_2") (pintype "passive"))
      (node (ref "R24") (pin "1") (pinfunction "1_1") (pintype "passive"))
      (node (ref "R46") (pin "1") (pinfunction "1_1") (pintype "passive"))
      (node (ref "R5") (pin "1") (pinfunction "1_1") (pintype "passive"))
      (node (ref "R6") (pin "1") (pinfunction "1_1") (pintype "passive"))
      (node (ref "R79") (pin "1") (pinfunction "1_1") (pintype "passive"))
      (node (ref "R8") (pin "2") (pinfunction "2_2") (pintype "passive"))
      (node (ref "R80") (pin "1") (pinfunction "1_1") (pintype "passive"))
      (node (ref "R81") (pin "1") (pinfunction "1_1") (pintype "passive"))
      (node (ref "U$19") (pin "3") (pinfunction "VIN_3") (pintype "bidirectional"))
      (node (ref "U$2") (pin "3") (pinfunction "VCC_3") (pintype "bidirectional"))
      (node (ref "U$2") (pin "4") (pinfunction "IN+_4") (pintype "bidirectional"))
      (node (ref "U$3") (pin "3") (pinfunction "VCC_3") (pintype "bidirectional"))
      (node (ref "U$3") (pin "5") (pinfunction "IN-_5") (pintype "bidirectional"))
      (node (ref "U$4") (pin "3") (pinfunction "VIN_3") (pintype "bidirectional"))
      (node (ref "U$5") (pin "3") (pinfunction "FB_3") (pintype "bidirectional"))
      (node (ref "U$5") (pin "4") (pinfunction "VOS_4") (pintype "bidirectional"))
      (node (ref "U$6") (pin "16") (pinfunction "AVCC_16") (pintype "bidirectional"))
      (node (ref "U$6") (pin "2") (pinfunction "DVCC_2") (pintype "bidirectional"))
      (node (ref "U$7") (pin "2") (pinfunction "C_2") (pintype "passive"))
      (node (ref "VCC") (pin "1") (pinfunction "1_1") (pintype "passive"))
    )
    (net (code "70") (name "unconnected-(U$4-PG-Pad6)") (class "Default")
      (node (ref "U$4") (pin "6") (pinfunction "PG_6") (pintype "bidirectional"))
    )
    (net (code "71") (name "unconnected-(U$6-P1.0{slash}TACLK{slash}ADC10CLK-Pad31)") (class "Default")
      (node (ref "U$6") (pin "31") (pinfunction "P1.0/TACLK/ADC10CLK_31") (pintype "bidirectional"))
    )
    (net (code "72") (name "unconnected-(U$6-P2.0{slash}ACLK{slash}A0-Pad8)") (class "Default")
      (node (ref "U$6") (pin "8") (pinfunction "P2.0/ACLK/A0_8") (pintype "bidirectional"))
    )
    (net (code "73") (name "unconnected-(U$6-P2.3{slash}TA1{slash}A3{slash}VREF−{slash}VEREF--Pad29)") (class "Default")
      (node (ref "U$6") (pin "29") (pinfunction "P2.3/TA1/A3/VREF−/VEREF-_29") (pintype "bidirectional"))
    )
    (net (code "74") (name "unconnected-(U$6-P2.4{slash}TA2{slash}A4{slash}VREF+{slash}VEREF+-Pad30)") (class "Default")
      (node (ref "U$6") (pin "30") (pinfunction "P2.4/TA2/A4/VREF+/VEREF+_30") (pintype "bidirectional"))
    )
    (net (code "75") (name "unconnected-(U$6-P2.5{slash}ROSC-Pad3)") (class "Default")
      (node (ref "U$6") (pin "3") (pinfunction "P2.5/ROSC_3") (pintype "bidirectional"))
    )
    (net (code "76") (name "unconnected-(U$6-P3.0{slash}UCB0STE{slash}UCA0CLK{slash}A5-Pad11)") (class "Default")
      (node (ref "U$6") (pin "11") (pinfunction "P3.0/UCB0STE/UCA0CLK/A5_11") (pintype "bidirectional"))
    )
    (net (code "77") (name "unconnected-(U$6-P3.3{slash}UCB0CLK{slash}UCA0STE-Pad14)") (class "Default")
      (node (ref "U$6") (pin "14") (pinfunction "P3.3/UCB0CLK/UCA0STE_14") (pintype "bidirectional"))
    )
    (net (code "78") (name "unconnected-(U$6-P3.4{slash}UCA0TXD{slash}UCA0SIMO-Pad25)") (class "Default")
      (node (ref "U$6") (pin "25") (pinfunction "P3.4/UCA0TXD/UCA0SIMO_25") (pintype "bidirectional"))
    )
    (net (code "79") (name "unconnected-(U$6-P3.5{slash}UCA0RXD{slash}UCA0SOMI-Pad26)") (class "Default")
      (node (ref "U$6") (pin "26") (pinfunction "P3.5/UCA0RXD/UCA0SOMI_26") (pintype "bidirectional"))
    )
    (net (code "80") (name "unconnected-(U$6-P4.0{slash}TB0-Pad17)") (class "Default")
      (node (ref "U$6") (pin "17") (pinfunction "P4.0/TB0_17") (pintype "bidirectional"))
    )
    (net (code "81") (name "unconnected-(U$6-P4.1{slash}TB1-Pad18)") (class "Default")
      (node (ref "U$6") (pin "18") (pinfunction "P4.1/TB1_18") (pintype "bidirectional"))
    )
    (net (code "82") (name "unconnected-(U$6-P4.2{slash}TB2-Pad19)") (class "Default")
      (node (ref "U$6") (pin "19") (pinfunction "P4.2/TB2_19") (pintype "bidirectional"))
    )
    (net (code "83") (name "unconnected-(U$6-P4.7{slash}TBCLK-Pad24)") (class "Default")
      (node (ref "U$6") (pin "24") (pinfunction "P4.7/TBCLK_24") (pintype "bidirectional"))
    )
    (net (code "84") (name "unconnected-(U$16-OC-Pad5)") (class "Default")
      (node (ref "U$16") (pin "5") (pinfunction "OC_5") (pintype "bidirectional"))
    )
    (net (code "85") (name "unconnected-(U$17-OC-Pad5)") (class "Default")
      (node (ref "U$17") (pin "5") (pinfunction "OC_5") (pintype "bidirectional"))
    )
    (net (code "86") (name "unconnected-(U$18-OC-Pad5)") (class "Default")
      (node (ref "U$18") (pin "5") (pinfunction "OC_5") (pintype "bidirectional"))
    )
    (net (code "87") (name "unconnected-(U$19-NC1-Pad1)") (class "Default")
      (node (ref "U$19") (pin "1") (pinfunction "NC1_1") (pintype "bidirectional"))
    )
    (net (code "88") (name "unconnected-(U$19-NC2-Pad5)") (class "Default")
      (node (ref "U$19") (pin "5") (pinfunction "NC2_5") (pintype "bidirectional"))
    )
    (net (code "89") (name "unconnected-(U$19-NC3-Pad6)") (class "Default")
      (node (ref "U$19") (pin "6") (pinfunction "NC3_6") (pintype "bidirectional"))
    )
  )
)
